# Pro_Shield_V2.net
KiCad netlist of a schematic drawn in EAGLE
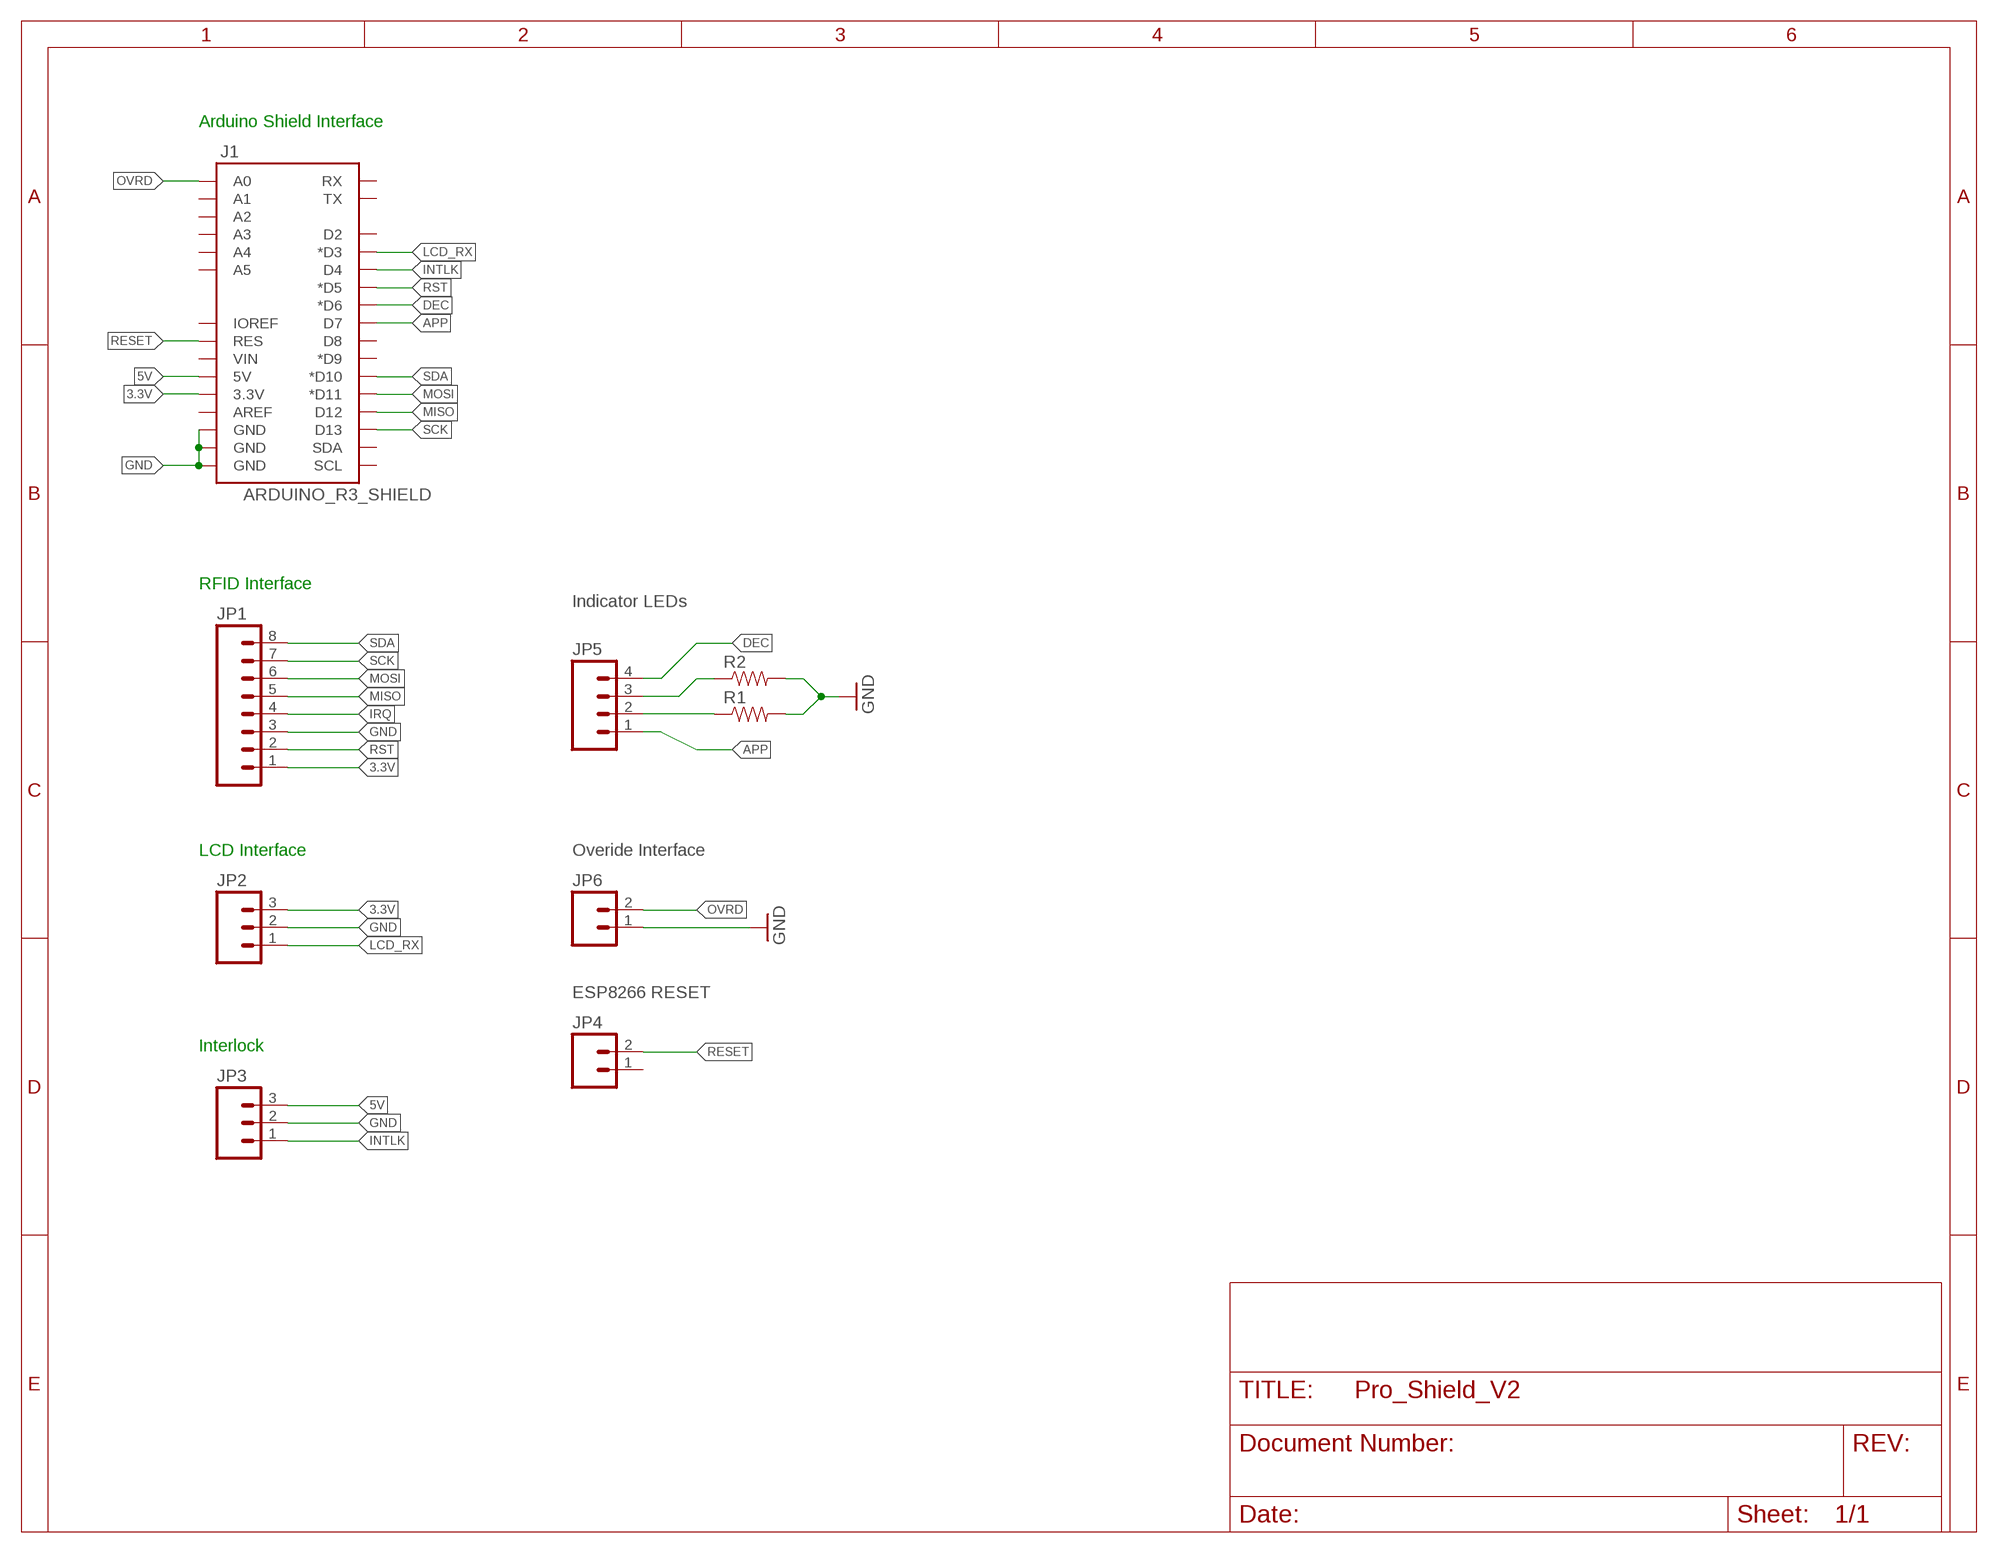
[diagram p0: schematic, sheet 1]

(export (version "E")
  (design (tool "Eeschema 10.0.6"))
  (components
    (comp (ref "J1")
      (value "ARDUINO_R3_SHIELD")
      (footprint "eagle-import:UNO_R3_SHIELD")
      (libsource (lib "eagle-import") (part "ARDUINO_R3_SHIELD"))
    )
    (comp (ref "JP1")
      (value "M08LONGPADS")
      (footprint "eagle-import:1X08_LONGPADS")
      (libsource (lib "eagle-import") (part "M08LONGPADS"))
    )
    (comp (ref "JP2")
      (value "M03LONGPADS")
      (footprint "eagle-import:1X03_LONGPADS")
      (libsource (lib "eagle-import") (part "M03LONGPADS"))
    )
    (comp (ref "JP3")
      (value "M03LONGPADS")
      (footprint "eagle-import:1X03_LONGPADS")
      (libsource (lib "eagle-import") (part "M03LONGPADS"))
    )
    (comp (ref "JP4")
      (value "M02LOCK_LONGPADS")
      (footprint "eagle-import:1X02_LOCK_LONGPADS")
      (libsource (lib "eagle-import") (part "M02LOCK_LONGPADS"))
    )
    (comp (ref "JP5")
      (value "M04LONGPADS")
      (footprint "eagle-import:1X04_LONGPADS")
      (libsource (lib "eagle-import") (part "M04LONGPADS"))
    )
    (comp (ref "JP6")
      (value "M02LOCK_LONGPADS")
      (footprint "eagle-import:1X02_LOCK_LONGPADS")
      (libsource (lib "eagle-import") (part "M02LOCK_LONGPADS"))
    )
    (comp (ref "R1")
      (value "RESISTORPTH-1/4W")
      (footprint "eagle-import:AXIAL-0.4")
      (libsource (lib "eagle-import") (part "RESISTORPTH-1/4W"))
    )
    (comp (ref "R2")
      (value "RESISTORPTH-1/4W")
      (footprint "eagle-import:AXIAL-0.4")
      (libsource (lib "eagle-import") (part "RESISTORPTH-1/4W"))
    )
  )
  (nets
    (net (code "1") (name "3.3V") (class "Default")
      (node (ref "J1") (pin "3.3V") (pinfunction "3.3V_3.3V") (pintype "bidirectional"))
      (node (ref "JP1") (pin "1") (pinfunction "1_1") (pintype "passive"))
      (node (ref "JP2") (pin "3") (pinfunction "3_3") (pintype "passive"))
    )
    (net (code "2") (name "5V") (class "Default")
      (node (ref "J1") (pin "5V") (pinfunction "5V_5V") (pintype "bidirectional"))
      (node (ref "JP3") (pin "3") (pinfunction "3_3") (pintype "passive"))
    )
    (net (code "3") (name "APP") (class "Default")
      (node (ref "J1") (pin "D7") (pinfunction "D7_D7") (pintype "bidirectional"))
      (node (ref "JP5") (pin "1") (pinfunction "1_1") (pintype "passive"))
    )
    (net (code "4") (name "DEC") (class "Default")
      (node (ref "J1") (pin "D6") (pinfunction "*D6_D6") (pintype "bidirectional"))
      (node (ref "JP5") (pin "4") (pinfunction "4_4") (pintype "passive"))
    )
    (net (code "5") (name "GND") (class "Default")
      (node (ref "J1") (pin "GND@0") (pinfunction "GND_GND@0") (pintype "bidirectional"))
      (node (ref "J1") (pin "GND@1") (pinfunction "GND_GND@1") (pintype "bidirectional"))
      (node (ref "J1") (pin "GND@2") (pinfunction "GND_GND@2") (pintype "bidirectional"))
      (node (ref "JP1") (pin "3") (pinfunction "3_3") (pintype "passive"))
      (node (ref "JP2") (pin "2") (pinfunction "2_2") (pintype "passive"))
      (node (ref "JP3") (pin "2") (pinfunction "2_2") (pintype "passive"))
      (node (ref "JP6") (pin "1") (pinfunction "1_1") (pintype "passive"))
      (node (ref "R1") (pin "P$2") (pinfunction "2_P$2") (pintype "passive"))
      (node (ref "R2") (pin "P$2") (pinfunction "2_P$2") (pintype "passive"))
    )
    (net (code "6") (name "INTLK") (class "Default")
      (node (ref "J1") (pin "D4") (pinfunction "D4_D4") (pintype "bidirectional"))
      (node (ref "JP3") (pin "1") (pinfunction "1_1") (pintype "passive"))
    )
    (net (code "7") (name "IRQ") (class "Default")
      (node (ref "JP1") (pin "4") (pinfunction "4_4") (pintype "passive"))
    )
    (net (code "8") (name "LCD_RX") (class "Default")
      (node (ref "J1") (pin "D3") (pinfunction "*D3_D3") (pintype "bidirectional"))
      (node (ref "JP2") (pin "1") (pinfunction "1_1") (pintype "passive"))
    )
    (net (code "9") (name "MISO") (class "Default")
      (node (ref "J1") (pin "D12") (pinfunction "D12_D12") (pintype "bidirectional"))
      (node (ref "JP1") (pin "5") (pinfunction "5_5") (pintype "passive"))
    )
    (net (code "10") (name "MOSI") (class "Default")
      (node (ref "J1") (pin "D11") (pinfunction "*D11_D11") (pintype "bidirectional"))
      (node (ref "JP1") (pin "6") (pinfunction "6_6") (pintype "passive"))
    )
    (net (code "11") (name "Net-(R1-1)") (class "Default")
      (node (ref "JP5") (pin "2") (pinfunction "2_2") (pintype "passive"))
      (node (ref "R1") (pin "P$1") (pinfunction "1_P$1") (pintype "passive"))
    )
    (net (code "12") (name "Net-(R2-1)") (class "Default")
      (node (ref "JP5") (pin "3") (pinfunction "3_3") (pintype "passive"))
      (node (ref "R2") (pin "P$1") (pinfunction "1_P$1") (pintype "passive"))
    )
    (net (code "13") (name "OVRD") (class "Default")
      (node (ref "J1") (pin "A0") (pinfunction "A0_A0") (pintype "bidirectional"))
      (node (ref "JP6") (pin "2") (pinfunction "2_2") (pintype "passive"))
    )
    (net (code "14") (name "RESET") (class "Default")
      (node (ref "J1") (pin "RES") (pinfunction "RES_RES") (pintype "bidirectional"))
      (node (ref "JP4") (pin "2") (pinfunction "2_2") (pintype "passive"))
    )
    (net (code "15") (name "RST") (class "Default")
      (node (ref "J1") (pin "D5") (pinfunction "*D5_D5") (pintype "bidirectional"))
      (node (ref "JP1") (pin "2") (pinfunction "2_2") (pintype "passive"))
    )
    (net (code "16") (name "SCK") (class "Default")
      (node (ref "J1") (pin "D13") (pinfunction "D13_D13") (pintype "bidirectional"))
      (node (ref "JP1") (pin "7") (pinfunction "7_7") (pintype "passive"))
    )
    (net (code "17") (name "SDA") (class "Default")
      (node (ref "J1") (pin "D10") (pinfunction "*D10_D10") (pintype "bidirectional"))
      (node (ref "JP1") (pin "8") (pinfunction "8_8") (pintype "passive"))
    )
    (net (code "18") (name "unconnected-(J1-*D9-PadD9)") (class "Default")
      (node (ref "J1") (pin "D9") (pinfunction "*D9_D9") (pintype "bidirectional"))
    )
    (net (code "19") (name "unconnected-(J1-PadA1)") (class "Default")
      (node (ref "J1") (pin "A1") (pinfunction "A1_A1") (pintype "bidirectional"))
    )
    (net (code "20") (name "unconnected-(J1-PadA2)") (class "Default")
      (node (ref "J1") (pin "A2") (pinfunction "A2_A2") (pintype "bidirectional"))
    )
    (net (code "21") (name "unconnected-(J1-PadA3)") (class "Default")
      (node (ref "J1") (pin "A3") (pinfunction "A3_A3") (pintype "bidirectional"))
    )
    (net (code "22") (name "unconnected-(J1-PadA4)") (class "Default")
      (node (ref "J1") (pin "A4") (pinfunction "A4_A4") (pintype "bidirectional"))
    )
    (net (code "23") (name "unconnected-(J1-PadA5)") (class "Default")
      (node (ref "J1") (pin "A5") (pinfunction "A5_A5") (pintype "bidirectional"))
    )
    (net (code "24") (name "unconnected-(J1-PadAREF)") (class "Default")
      (node (ref "J1") (pin "AREF") (pinfunction "AREF_AREF") (pintype "bidirectional"))
    )
    (net (code "25") (name "unconnected-(J1-PadD2)") (class "Default")
      (node (ref "J1") (pin "D2") (pinfunction "D2_D2") (pintype "bidirectional"))
    )
    (net (code "26") (name "unconnected-(J1-PadD8)") (class "Default")
      (node (ref "J1") (pin "D8") (pinfunction "D8_D8") (pintype "bidirectional"))
    )
    (net (code "27") (name "unconnected-(J1-PadIOREF)") (class "Default")
      (node (ref "J1") (pin "IOREF") (pinfunction "IOREF_IOREF") (pintype "bidirectional"))
    )
    (net (code "28") (name "unconnected-(J1-PadRX)") (class "Default")
      (node (ref "J1") (pin "RX") (pinfunction "RX_RX") (pintype "bidirectional"))
    )
    (net (code "29") (name "unconnected-(J1-PadSCL)") (class "Default")
      (node (ref "J1") (pin "SCL") (pinfunction "SCL_SCL") (pintype "bidirectional"))
    )
    (net (code "30") (name "unconnected-(J1-PadSDA)") (class "Default")
      (node (ref "J1") (pin "SDA") (pinfunction "SDA_SDA") (pintype "bidirectional"))
    )
    (net (code "31") (name "unconnected-(J1-PadTX)") (class "Default")
      (node (ref "J1") (pin "TX") (pinfunction "TX_TX") (pintype "bidirectional"))
    )
    (net (code "32") (name "unconnected-(J1-PadVIN)") (class "Default")
      (node (ref "J1") (pin "VIN") (pinfunction "VIN_VIN") (pintype "bidirectional"))
    )
    (net (code "33") (name "unconnected-(JP4-Pad1)") (class "Default")
      (node (ref "JP4") (pin "1") (pinfunction "1_1") (pintype "passive"))
    )
  )
)
